# NRF2401.net
KiCad netlist of a schematic drawn in Altium Designer
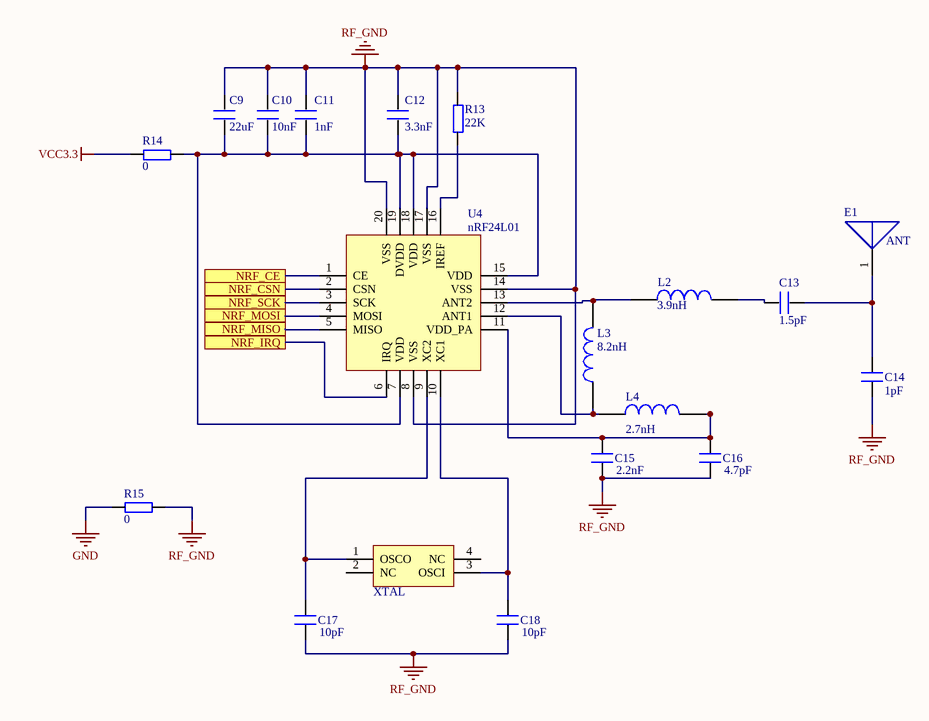
[diagram p0: NRF2401.SchDoc]

(export (version "E")
  (design (tool "Eeschema 10.0.6"))
  (components
    (comp (ref "C9") (value "22uF") (footprint "0603P") (libsource (lib "Explorer STM32F407封装库") (part "C")))
    (comp (ref "C10") (value "10nF") (footprint "0603P") (libsource (lib "Explorer STM32F407封装库") (part "C")))
    (comp (ref "C11") (value "1nF") (footprint "0603P") (libsource (lib "Explorer STM32F407封装库") (part "C")))
    (comp (ref "C12")
      (value "3.3nF")
      (footprint "0603P")
      (libsource (lib "Explorer STM32F407封装库") (part "C"))
    )
    (comp (ref "C13")
      (value "1.5pF")
      (footprint "0603P")
      (libsource (lib "Explorer STM32F407封装库") (part "C"))
    )
    (comp (ref "C14") (value "1pF") (footprint "0603P") (libsource (lib "Explorer STM32F407封装库") (part "C")))
    (comp (ref "C15")
      (value "2.2nF")
      (footprint "0603P")
      (libsource (lib "Explorer STM32F407封装库") (part "C"))
    )
    (comp (ref "C16")
      (value "4.7pF")
      (footprint "0603P")
      (libsource (lib "Explorer STM32F407封装库") (part "C"))
    )
    (comp (ref "C17") (value "10pF") (footprint "0603P") (libsource (lib "Explorer STM32F407封装库") (part "C")))
    (comp (ref "C18") (value "10pF") (footprint "0603P") (libsource (lib "Explorer STM32F407封装库") (part "C")))
    (comp (ref "E1")
      (value "ANT")
      (footprint "ANT")
      (fields (field (name "PUBLISHER") "mazhongwei"))
      (libsource (lib "RoboFly") (part "ANT"))
    )
    (comp (ref "L2")
      (value "INDUCTOR")
      (footprint "0402L")
      (fields (field (name "ALTIUM_UNNAMED_1") "3.9nH"))
      (libsource (lib "") (part "INDUCTOR_1"))
    )
    (comp (ref "L3")
      (value "INDUCTOR")
      (footprint "0402L")
      (fields (field (name "ALTIUM_UNNAMED_1") "8.2nH"))
      (libsource (lib "电感") (part "INDUCTOR"))
    )
    (comp (ref "L4")
      (value "INDUCTOR")
      (footprint "0402L")
      (fields (field (name "ALTIUM_UNNAMED_1") "2.7nH"))
      (libsource (lib "") (part "INDUCTOR_1"))
    )
    (comp (ref "R13") (value "22K") (footprint "0603P") (libsource (lib "Explorer STM32F407封装库") (part "R")))
    (comp (ref "R14") (value "0") (footprint "0603P") (libsource (lib "Explorer STM32F407封装库") (part "R")))
    (comp (ref "R15") (value "0") (footprint "0603P") (libsource (lib "Explorer STM32F407封装库") (part "R")))
    (comp (ref "U4") (value "nRF24L01") (footprint "QFN20") (libsource (lib "RoboFly") (part "nRF24L01")))
    (comp (ref "XTAL1")
      (value "XTAL")
      (footprint "SMD-3225_4P")
      (description "XTAL16M")
      (libsource (lib "RoboFly") (part "XTAL16M"))
    )
  )
  (nets
    (net (code "1") (name "/NRF_CE") (class "Default")
      (node (ref "U4") (pin "1") (pinfunction "CE_1") (pintype "passive"))
    )
    (net (code "2") (name "/NRF_CSN") (class "Default")
      (node (ref "U4") (pin "2") (pinfunction "CSN_2") (pintype "passive"))
    )
    (net (code "3") (name "/NRF_IRQ") (class "Default")
      (node (ref "U4") (pin "6") (pinfunction "IRQ_6") (pintype "passive"))
    )
    (net (code "4") (name "/NRF_MISO") (class "Default")
      (node (ref "U4") (pin "5") (pinfunction "MISO_5") (pintype "passive"))
    )
    (net (code "5") (name "/NRF_MOSI") (class "Default")
      (node (ref "U4") (pin "4") (pinfunction "MOSI_4") (pintype "passive"))
    )
    (net (code "6") (name "/NRF_SCK") (class "Default")
      (node (ref "U4") (pin "3") (pinfunction "SCK_3") (pintype "passive"))
    )
    (net (code "7") (name "GND") (class "Default") (node (ref "R15") (pin "1") (pintype "passive")))
    (net (code "8") (name "Net-(C13-Pad1)") (class "Default")
      (node (ref "C13") (pin "1") (pintype "passive"))
      (node (ref "L2") (pin "2") (pinfunction "2_2") (pintype "passive"))
    )
    (net (code "9") (name "Net-(C13-Pad2)") (class "Default")
      (node (ref "C13") (pin "2") (pintype "passive"))
      (node (ref "C14") (pin "2") (pintype "passive"))
      (node (ref "E1") (pin "1") (pinfunction "1_1") (pintype "passive"))
    )
    (net (code "10") (name "Net-(U4-ANT1)") (class "Default")
      (node (ref "L3") (pin "1") (pinfunction "1_1") (pintype "passive"))
      (node (ref "L4") (pin "1") (pinfunction "1_1") (pintype "passive"))
      (node (ref "U4") (pin "12") (pinfunction "ANT1_12") (pintype "passive"))
    )
    (net (code "11") (name "Net-(U4-ANT2)") (class "Default")
      (node (ref "L2") (pin "1") (pinfunction "1_1") (pintype "passive"))
      (node (ref "L3") (pin "2") (pinfunction "2_2") (pintype "passive"))
      (node (ref "U4") (pin "13") (pinfunction "ANT2_13") (pintype "passive"))
    )
    (net (code "12") (name "Net-(U4-DVDD)") (class "Default")
      (node (ref "C10") (pin "2") (pintype "passive"))
      (node (ref "C11") (pin "2") (pintype "passive"))
      (node (ref "C12") (pin "2") (pintype "passive"))
      (node (ref "C9") (pin "2") (pintype "passive"))
      (node (ref "R14") (pin "2") (pintype "passive"))
      (node (ref "U4") (pin "15") (pinfunction "VDD_15") (pintype "passive"))
      (node (ref "U4") (pin "18") (pinfunction "VDD_18") (pintype "passive"))
      (node (ref "U4") (pin "19") (pinfunction "DVDD_19") (pintype "passive"))
      (node (ref "U4") (pin "7") (pinfunction "VDD_7") (pintype "passive"))
    )
    (net (code "13") (name "Net-(U4-IREF)") (class "Default")
      (node (ref "R13") (pin "1") (pintype "passive"))
      (node (ref "U4") (pin "16") (pinfunction "IREF_16") (pintype "passive"))
    )
    (net (code "14") (name "Net-(U4-VDD_PA)") (class "Default")
      (node (ref "C15") (pin "1") (pintype "passive"))
      (node (ref "C16") (pin "1") (pintype "passive"))
      (node (ref "L4") (pin "2") (pinfunction "2_2") (pintype "passive"))
      (node (ref "U4") (pin "11") (pinfunction "VDD_PA_11") (pintype "passive"))
    )
    (net (code "15") (name "Net-(U4-XC1)") (class "Default")
      (node (ref "C18") (pin "1") (pintype "passive"))
      (node (ref "U4") (pin "10") (pinfunction "XC1_10") (pintype "passive"))
      (node (ref "XTAL1") (pin "3") (pinfunction "OSCI_3") (pintype "passive"))
    )
    (net (code "16") (name "Net-(U4-XC2)") (class "Default")
      (node (ref "C17") (pin "1") (pintype "passive"))
      (node (ref "U4") (pin "9") (pinfunction "XC2_9") (pintype "passive"))
      (node (ref "XTAL1") (pin "1") (pinfunction "OSCO_1") (pintype "passive"))
    )
    (net (code "17") (name "RF_GND") (class "Default")
      (node (ref "C10") (pin "1") (pintype "passive"))
      (node (ref "C11") (pin "1") (pintype "passive"))
      (node (ref "C12") (pin "1") (pintype "passive"))
      (node (ref "C14") (pin "1") (pintype "passive"))
      (node (ref "C15") (pin "2") (pintype "passive"))
      (node (ref "C16") (pin "2") (pintype "passive"))
      (node (ref "C17") (pin "2") (pintype "passive"))
      (node (ref "C18") (pin "2") (pintype "passive"))
      (node (ref "C9") (pin "1") (pintype "passive"))
      (node (ref "R13") (pin "2") (pintype "passive"))
      (node (ref "R15") (pin "2") (pintype "passive"))
      (node (ref "U4") (pin "14") (pinfunction "VSS_14") (pintype "passive"))
      (node (ref "U4") (pin "17") (pinfunction "VSS_17") (pintype "passive"))
      (node (ref "U4") (pin "20") (pinfunction "VSS_20") (pintype "passive"))
      (node (ref "U4") (pin "8") (pinfunction "VSS_8") (pintype "passive"))
    )
    (net (code "18") (name "VCC3.3") (class "Default") (node (ref "R14") (pin "1") (pintype "passive")))
    (net (code "19") (name "unconnected-(XTAL1-NC-Pad2)") (class "Default")
      (node (ref "XTAL1") (pin "2") (pinfunction "NC_2") (pintype "passive"))
    )
    (net (code "20") (name "unconnected-(XTAL1-NC-Pad4)") (class "Default")
      (node (ref "XTAL1") (pin "4") (pinfunction "NC_4") (pintype "passive"))
    )
  )
)
